# Sheet2.net
KiCad netlist of a schematic drawn in Altium Designer
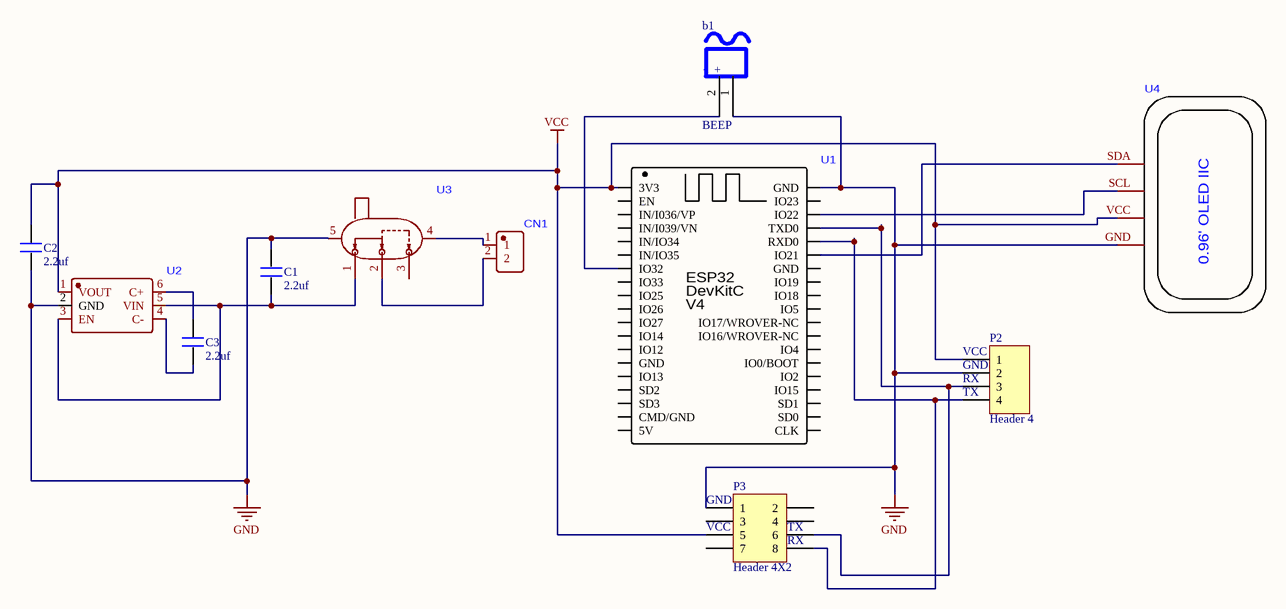
[diagram p0: Sheet2.SchDoc]

(export (version "E")
  (design (tool "Eeschema 10.0.6"))
  (components
    (comp (ref "b1") (value "BEEP") (footprint "beep") (libsource (lib "EF_Library") (part "BEEP")))
    (comp (ref "C1") (value "2.2uf") (footprint "C_0603") (libsource (lib "EF_Library") (part "C")))
    (comp (ref "C2") (value "2.2uf") (footprint "C_0603") (libsource (lib "EF_Library") (part "C")))
    (comp (ref "C3") (value "2.2uf") (footprint "C_0603") (libsource (lib "EF_Library") (part "C")))
    (comp (ref "CN1")
      (value "~")
      (footprint "XH2.54-2P_2024-04-30:CONN-TH_2P-P2.50-XH2.54-2P")
      (libsource (lib "altium-import") (part "root_0_XH2.54*2P_直插_"))
    )
    (comp (ref "P2")
      (value "Header 4")
      (footprint "HDR1X4")
      (description "Header, 4-Pin")
      (fields (field (name "PUBLISHER") "Altium Limited"))
      (libsource (lib "Miscellaneous Connectors") (part "Header 4"))
    )
    (comp (ref "P3")
      (value "Header 4X2")
      (footprint "HDR2X4")
      (description "Header, 4-Pin, Dual row")
      (fields (field (name "PUBLISHER") "Altium Limited"))
      (libsource (lib "Miscellaneous Connectors") (part "Header 4X2"))
    )
    (comp (ref "U1")
      (value "~")
      (footprint "ESP32DEVKITC_2024-03-25:ESP32DEVKITC")
      (libsource (lib "altium-import") (part "root_0_ESP32DevKitC_"))
    )
    (comp (ref "U2")
      (value "~")
      (footprint "SOT-23-6_L2.9-W1.6-P0.95-LS2.8-BL-1_2024-04-30:SOT-23-6_L2.9-W1.6-P0.95-LS2.8-BL-1")
      (libsource (lib "altium-import") (part "root_0_PW5410B_"))
    )
    (comp (ref "U3")
      (value "~")
      (footprint "switch-SS12D11-G5_2024-05-03:SW-TH_KH-SS12D11-G5")
      (libsource (lib "altium-import") (part "root_0_KH-SS12D11-G5_"))
    )
    (comp (ref "U4")
      (value "~")
      (footprint "0.96OLEDIIC")
      (libsource (lib "altium-import") (part "root_1_0.96OLED_4P_1_"))
    )
  )
  (nets
    (net (code "1") (name "GND") (class "Default")
      (node (ref "C1") (pin "2") (pinfunction "2_2") (pintype "passive"))
      (node (ref "C2") (pin "1") (pintype "passive"))
      (node (ref "P2") (pin "2") (pinfunction "2_2") (pintype "passive"))
      (node (ref "P3") (pin "1") (pinfunction "1_1") (pintype "passive"))
      (node (ref "U1") (pin "38") (pinfunction "GND_38") (pintype "passive"))
      (node (ref "U2") (pin "2") (pinfunction "GND_2") (pintype "passive"))
      (node (ref "U3") (pin "5") (pinfunction "5_5") (pintype "passive"))
      (node (ref "U4") (pin "GND") (pinfunction "GND_GND") (pintype "passive"))
      (node (ref "b1") (pin "1") (pinfunction "1_1") (pintype "passive"))
    )
    (net (code "2") (name "Net-(CN1-Pad1)") (class "Default")
      (node (ref "CN1") (pin "1") (pinfunction "1_1") (pintype "passive"))
      (node (ref "U3") (pin "4") (pinfunction "4_4") (pintype "passive"))
    )
    (net (code "3") (name "Net-(CN1-Pad2)") (class "Default")
      (node (ref "CN1") (pin "2") (pinfunction "2_2") (pintype "passive"))
      (node (ref "U3") (pin "2") (pinfunction "2_2") (pintype "passive"))
    )
    (net (code "4") (name "Net-(U1-IO21)") (class "Default")
      (node (ref "U1") (pin "33") (pinfunction "IO21_33") (pintype "passive"))
      (node (ref "U4") (pin "SDA") (pinfunction "SDA_SDA") (pintype "passive"))
    )
    (net (code "5") (name "Net-(U1-IO22)") (class "Default")
      (node (ref "U1") (pin "36") (pinfunction "IO22_36") (pintype "passive"))
      (node (ref "U4") (pin "SCL") (pinfunction "SCL_SCL") (pintype "passive"))
    )
    (net (code "6") (name "Net-(U1-IO32)") (class "Default")
      (node (ref "U1") (pin "7") (pinfunction "IO32_7") (pintype "passive"))
      (node (ref "b1") (pin "2") (pinfunction "2_2") (pintype "passive"))
    )
    (net (code "7") (name "Net-(U1-RXD0)") (class "Default")
      (node (ref "P2") (pin "4") (pinfunction "4_4") (pintype "passive"))
      (node (ref "P3") (pin "8") (pinfunction "8_8") (pintype "passive"))
      (node (ref "U1") (pin "34") (pinfunction "RXD0_34") (pintype "passive"))
    )
    (net (code "8") (name "Net-(U1-TXD0)") (class "Default")
      (node (ref "P2") (pin "3") (pinfunction "3_3") (pintype "passive"))
      (node (ref "P3") (pin "6") (pinfunction "6_6") (pintype "passive"))
      (node (ref "U1") (pin "35") (pinfunction "TXD0_35") (pintype "passive"))
    )
    (net (code "9") (name "Net-(U2-C+)") (class "Default")
      (node (ref "C3") (pin "2") (pinfunction "2_2") (pintype "passive"))
      (node (ref "U2") (pin "6") (pinfunction "C+_6") (pintype "passive"))
    )
    (net (code "10") (name "Net-(U2-C-)") (class "Default")
      (node (ref "C3") (pin "1") (pintype "passive"))
      (node (ref "U2") (pin "4") (pinfunction "C-_4") (pintype "passive"))
    )
    (net (code "11") (name "Net-(U2-EN)") (class "Default")
      (node (ref "C1") (pin "1") (pintype "passive"))
      (node (ref "U2") (pin "3") (pinfunction "EN_3") (pintype "passive"))
      (node (ref "U2") (pin "5") (pinfunction "VIN_5") (pintype "passive"))
      (node (ref "U3") (pin "1") (pinfunction "1_1") (pintype "passive"))
    )
    (net (code "12") (name "VCC") (class "Default")
      (node (ref "C2") (pin "2") (pinfunction "2_2") (pintype "passive"))
      (node (ref "P2") (pin "1") (pinfunction "1_1") (pintype "passive"))
      (node (ref "P3") (pin "5") (pinfunction "5_5") (pintype "passive"))
      (node (ref "U1") (pin "1") (pinfunction "3V3_1") (pintype "passive"))
      (node (ref "U2") (pin "1") (pinfunction "VOUT_1") (pintype "passive"))
      (node (ref "U4") (pin "VCC") (pinfunction "VCC_VCC") (pintype "passive"))
    )
    (net (code "13") (name "unconnected-(P3-Pad2)") (class "Default")
      (node (ref "P3") (pin "2") (pinfunction "2_2") (pintype "passive"))
    )
    (net (code "14") (name "unconnected-(P3-Pad3)") (class "Default")
      (node (ref "P3") (pin "3") (pinfunction "3_3") (pintype "passive"))
    )
    (net (code "15") (name "unconnected-(P3-Pad4)") (class "Default")
      (node (ref "P3") (pin "4") (pinfunction "4_4") (pintype "passive"))
    )
    (net (code "16") (name "unconnected-(P3-Pad7)") (class "Default")
      (node (ref "P3") (pin "7") (pinfunction "7_7") (pintype "passive"))
    )
    (net (code "17") (name "unconnected-(U1-5V-Pad19)") (class "Default")
      (node (ref "U1") (pin "19") (pinfunction "5V_19") (pintype "passive"))
    )
    (net (code "18") (name "unconnected-(U1-CLK-Pad20)") (class "Default")
      (node (ref "U1") (pin "20") (pinfunction "CLK_20") (pintype "passive"))
    )
    (net (code "19") (name "unconnected-(U1-CMD{slash}GND-Pad18)") (class "Default")
      (node (ref "U1") (pin "18") (pinfunction "CMD/GND_18") (pintype "passive"))
    )
    (net (code "20") (name "unconnected-(U1-EN-Pad2)") (class "Default")
      (node (ref "U1") (pin "2") (pinfunction "EN_2") (pintype "passive"))
    )
    (net (code "21") (name "unconnected-(U1-GND-Pad14)") (class "Default")
      (node (ref "U1") (pin "14") (pinfunction "GND_14") (pintype "passive"))
    )
    (net (code "22") (name "unconnected-(U1-GND-Pad32)") (class "Default")
      (node (ref "U1") (pin "32") (pinfunction "GND_32") (pintype "passive"))
    )
    (net (code "23") (name "unconnected-(U1-IN{slash}I036{slash}VP-Pad3)") (class "Default")
      (node (ref "U1") (pin "3") (pinfunction "IN/I036/VP_3") (pintype "passive"))
    )
    (net (code "24") (name "unconnected-(U1-IN{slash}I039{slash}VN-Pad4)") (class "Default")
      (node (ref "U1") (pin "4") (pinfunction "IN/I039/VN_4") (pintype "passive"))
    )
    (net (code "25") (name "unconnected-(U1-IN{slash}IO34-Pad5)") (class "Default")
      (node (ref "U1") (pin "5") (pinfunction "IN/IO34_5") (pintype "passive"))
    )
    (net (code "26") (name "unconnected-(U1-IN{slash}IO35-Pad6)") (class "Default")
      (node (ref "U1") (pin "6") (pinfunction "IN/IO35_6") (pintype "passive"))
    )
    (net (code "27") (name "unconnected-(U1-IO0{slash}BOOT-Pad25)") (class "Default")
      (node (ref "U1") (pin "25") (pinfunction "IO0/BOOT_25") (pintype "passive"))
    )
    (net (code "28") (name "unconnected-(U1-IO2-Pad24)") (class "Default")
      (node (ref "U1") (pin "24") (pinfunction "IO2_24") (pintype "passive"))
    )
    (net (code "29") (name "unconnected-(U1-IO4-Pad26)") (class "Default")
      (node (ref "U1") (pin "26") (pinfunction "IO4_26") (pintype "passive"))
    )
    (net (code "30") (name "unconnected-(U1-IO5-Pad29)") (class "Default")
      (node (ref "U1") (pin "29") (pinfunction "IO5_29") (pintype "passive"))
    )
    (net (code "31") (name "unconnected-(U1-IO12-Pad13)") (class "Default")
      (node (ref "U1") (pin "13") (pinfunction "IO12_13") (pintype "passive"))
    )
    (net (code "32") (name "unconnected-(U1-IO13-Pad15)") (class "Default")
      (node (ref "U1") (pin "15") (pinfunction "IO13_15") (pintype "passive"))
    )
    (net (code "33") (name "unconnected-(U1-IO14-Pad12)") (class "Default")
      (node (ref "U1") (pin "12") (pinfunction "IO14_12") (pintype "passive"))
    )
    (net (code "34") (name "unconnected-(U1-IO15-Pad23)") (class "Default")
      (node (ref "U1") (pin "23") (pinfunction "IO15_23") (pintype "passive"))
    )
    (net (code "35") (name "unconnected-(U1-IO16{slash}WROVER-NC-Pad27)") (class "Default")
      (node (ref "U1") (pin "27") (pinfunction "IO16/WROVER-NC_27") (pintype "passive"))
    )
    (net (code "36") (name "unconnected-(U1-IO17{slash}WROVER-NC-Pad28)") (class "Default")
      (node (ref "U1") (pin "28") (pinfunction "IO17/WROVER-NC_28") (pintype "passive"))
    )
    (net (code "37") (name "unconnected-(U1-IO18-Pad30)") (class "Default")
      (node (ref "U1") (pin "30") (pinfunction "IO18_30") (pintype "passive"))
    )
    (net (code "38") (name "unconnected-(U1-IO19-Pad31)") (class "Default")
      (node (ref "U1") (pin "31") (pinfunction "IO19_31") (pintype "passive"))
    )
    (net (code "39") (name "unconnected-(U1-IO23-Pad37)") (class "Default")
      (node (ref "U1") (pin "37") (pinfunction "IO23_37") (pintype "passive"))
    )
    (net (code "40") (name "unconnected-(U1-IO25-Pad9)") (class "Default")
      (node (ref "U1") (pin "9") (pinfunction "IO25_9") (pintype "passive"))
    )
    (net (code "41") (name "unconnected-(U1-IO26-Pad10)") (class "Default")
      (node (ref "U1") (pin "10") (pinfunction "IO26_10") (pintype "passive"))
    )
    (net (code "42") (name "unconnected-(U1-IO27-Pad11)") (class "Default")
      (node (ref "U1") (pin "11") (pinfunction "IO27_11") (pintype "passive"))
    )
    (net (code "43") (name "unconnected-(U1-IO33-Pad8)") (class "Default")
      (node (ref "U1") (pin "8") (pinfunction "IO33_8") (pintype "passive"))
    )
    (net (code "44") (name "unconnected-(U1-SD0-Pad21)") (class "Default")
      (node (ref "U1") (pin "21") (pinfunction "SD0_21") (pintype "passive"))
    )
    (net (code "45") (name "unconnected-(U1-SD1-Pad22)") (class "Default")
      (node (ref "U1") (pin "22") (pinfunction "SD1_22") (pintype "passive"))
    )
    (net (code "46") (name "unconnected-(U1-SD2-Pad16)") (class "Default")
      (node (ref "U1") (pin "16") (pinfunction "SD2_16") (pintype "passive"))
    )
    (net (code "47") (name "unconnected-(U1-SD3-Pad17)") (class "Default")
      (node (ref "U1") (pin "17") (pinfunction "SD3_17") (pintype "passive"))
    )
    (net (code "48") (name "unconnected-(U3-Pad3)") (class "Default")
      (node (ref "U3") (pin "3") (pinfunction "3_3") (pintype "passive"))
    )
  )
)
